# Primary.net
KiCad netlist of a schematic drawn in Altium Designer
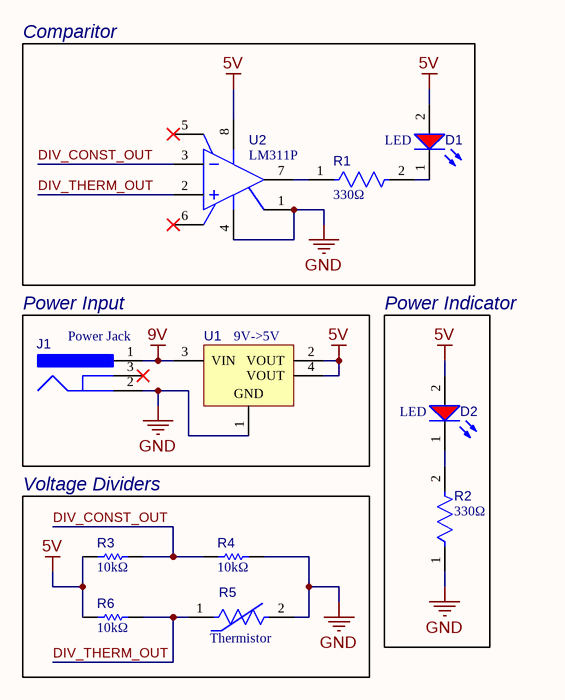
[diagram p0: Primary.SchDoc]

(export (version "E")
  (design (tool "Eeschema 10.0.6"))
  (components
    (comp (ref "D1")
      (value "LED")
      (footprint "WL-SMCW_1206_150120xx75000")
      (description "WL-SMCW SMT Mono-Color Chip LED Waterclear")
      (libsource (lib "Altium Content Vault") (part "LED_Red_2A-1K"))
    )
    (comp (ref "D2")
      (value "LED")
      (footprint "WL-SMCW_1206_150120xx75000")
      (description "WL-SMCW SMT Mono-Color Chip LED Waterclear")
      (libsource (lib "Altium Content Vault") (part "LED_Red_2A-1K"))
    )
    (comp (ref "J1")
      (value "Power Jack")
      (footprint "CUI-PJ-002A_V")
      (fields (field (name "MANUFACTURER") "CUIInc."))
      (libsource (lib "Altium Content Vault") (part "JACK-2CD3-RN_B"))
    )
    (comp (ref "R1")
      (value "330Ω")
      (footprint "FP-CRCW1206-e3-IPC_A")
      (description "RES Thick Film, 330Ω, 1%, 0.25W, 100ppm/°C, 1206")
      (fields (field (name "TOLERANCE") "1%"))
      (libsource (lib "Altium Content Vault") (part "1029c3af85768c4190bb7ad29bc67b5"))
    )
    (comp (ref "R2")
      (value "330Ω")
      (footprint "FP-CRCW1206-e3-IPC_A")
      (description "RES Thick Film, 330Ω, 1%, 0.25W, 100ppm/°C, 1206")
      (fields (field (name "TOLERANCE") "1%"))
      (libsource (lib "Altium Content Vault") (part "1029c3af85768c4190bb7ad29bc67b5"))
    )
    (comp (ref "R3")
      (value "10kΩ")
      (footprint "RESC3116X65X40ML10T20")
      (description "Chip Resistor, 10 KOhm, +/- 1%, 0.25 W, -55 to 155 degC, 1206 (3216 Metric), RoHS, Tape and Reel")
      (fields (field (name "TOLERANCE") "1%") (field (name "MANUFACTURER") "Yageo"))
      (libsource (lib "Altium Content Vault") (part "RES-2"))
    )
    (comp (ref "R4")
      (value "10kΩ")
      (footprint "RESC3116X65X40ML10T20")
      (description "Chip Resistor, 10 KOhm, +/- 1%, 0.25 W, -55 to 155 degC, 1206 (3216 Metric), RoHS, Tape and Reel")
      (fields (field (name "TOLERANCE") "1%") (field (name "MANUFACTURER") "Yageo"))
      (libsource (lib "Altium Content Vault") (part "RES-2"))
    )
    (comp (ref "R5")
      (value "Thermistor")
      (footprint "FP-NCP18-0_15-IPC_A")
      (description "NTC Thermistor for Temperature Sensor, 0603, 10kΩ, 1%, 0.1mA, 5V")
      (fields (field (name "TOLERANCE") "1%"))
      (libsource (lib "Altium Content Vault") (part "3b148a6ebabc5fb4d708a66c052d352"))
    )
    (comp (ref "R6")
      (value "10kΩ")
      (footprint "RESC3116X65X40ML10T20")
      (description "Chip Resistor, 10 KOhm, +/- 1%, 0.25 W, -55 to 155 degC, 1206 (3216 Metric), RoHS, Tape and Reel")
      (fields (field (name "TOLERANCE") "1%") (field (name "MANUFACTURER") "Yageo"))
      (libsource (lib "Altium Content Vault") (part "RES-2"))
    )
    (comp (ref "U1")
      (value "9V->5V")
      (footprint "SOT-223_L")
      (description "Fixed Low Drop Positive Voltage Regulator, 5V, 4-Pin SOT-223, Tape and Reel")
      (libsource (lib "Altium Content Vault") (part "PM-REG-LD1117-SOT4"))
    )
    (comp (ref "U2")
      (value "LM311P")
      (footprint "FP-P0008A-MFG")
      (fields (field (name "TOLERANCE") "1%"))
      (libsource (lib "Altium Content Vault") (part "b2b1c66385073ed7f685b7e01cc60c1"))
    )
  )
  (nets
    (net (code "1") (name "/DIV_CONST_OUT") (class "Default")
      (node (ref "R3") (pin "2") (pinfunction "2_2") (pintype "passive"))
      (node (ref "R4") (pin "1") (pinfunction "1_1") (pintype "passive"))
      (node (ref "U2") (pin "3") (pinfunction "IN-_3") (pintype "tri_state"))
    )
    (net (code "2") (name "/DIV_THERM_OUT") (class "Default")
      (node (ref "R5") (pin "1") (pinfunction "1_1") (pintype "passive"))
      (node (ref "R6") (pin "2") (pinfunction "2_2") (pintype "passive"))
      (node (ref "U2") (pin "2") (pinfunction "IN+_2") (pintype "tri_state"))
    )
    (net (code "3") (name "5V") (class "Default")
      (node (ref "D1") (pin "2") (pinfunction "A_2") (pintype "passive"))
      (node (ref "D2") (pin "2") (pinfunction "A_2") (pintype "passive"))
      (node (ref "R3") (pin "1") (pinfunction "1_1") (pintype "passive"))
      (node (ref "R6") (pin "1") (pinfunction "1_1") (pintype "passive"))
      (node (ref "U1") (pin "2") (pinfunction "VOUT_2") (pintype "power_in"))
      (node (ref "U1") (pin "4") (pinfunction "VOUT_4") (pintype "power_in"))
      (node (ref "U2") (pin "8") (pinfunction "VCC+_8") (pintype "power_in"))
    )
    (net (code "4") (name "9V") (class "Default")
      (node (ref "J1") (pin "1") (pinfunction "1_1") (pintype "passive"))
      (node (ref "U1") (pin "3") (pinfunction "VIN_3") (pintype "power_in"))
    )
    (net (code "5") (name "GND") (class "Default")
      (node (ref "J1") (pin "2") (pinfunction "2_2") (pintype "passive"))
      (node (ref "R2") (pin "1") (pinfunction "1_1") (pintype "passive"))
      (node (ref "R4") (pin "2") (pinfunction "2_2") (pintype "passive"))
      (node (ref "R5") (pin "2") (pinfunction "2_2") (pintype "passive"))
      (node (ref "U1") (pin "1") (pinfunction "GND_1") (pintype "power_in"))
      (node (ref "U2") (pin "1") (pinfunction "EMIT_OUT_1") (pintype "open_emitter"))
      (node (ref "U2") (pin "4") (pinfunction "VCC-_4") (pintype "power_in"))
    )
    (net (code "6") (name "Net-(D1-K)") (class "Default")
      (node (ref "D1") (pin "1") (pinfunction "K_1") (pintype "passive"))
      (node (ref "R1") (pin "2") (pinfunction "2_2") (pintype "passive"))
    )
    (net (code "7") (name "Net-(D2-K)") (class "Default")
      (node (ref "D2") (pin "1") (pinfunction "K_1") (pintype "passive"))
      (node (ref "R2") (pin "2") (pinfunction "2_2") (pintype "passive"))
    )
    (net (code "8") (name "Net-(U2-COL_OUT)") (class "Default")
      (node (ref "R1") (pin "1") (pinfunction "1_1") (pintype "passive"))
      (node (ref "U2") (pin "7") (pinfunction "COL_OUT_7") (pintype "open_collector"))
    )
    (net (code "9") (name "unconnected-(J1-Pad3)") (class "Default")
      (node (ref "J1") (pin "3") (pinfunction "3_3") (pintype "passive+no_connect"))
    )
    (net (code "10") (name "unconnected-(U2-BALANCE-Pad5)") (class "Default")
      (node (ref "U2") (pin "5") (pinfunction "BALANCE_5") (pintype "passive+no_connect"))
    )
    (net (code "11") (name "unconnected-(U2-BAL{slash}STRB-Pad6)") (class "Default")
      (node (ref "U2") (pin "6") (pinfunction "BAL/STRB_6") (pintype "passive+no_connect"))
    )
  )
)
